# Drive_X.net
KiCad netlist of a schematic drawn in Altium Designer
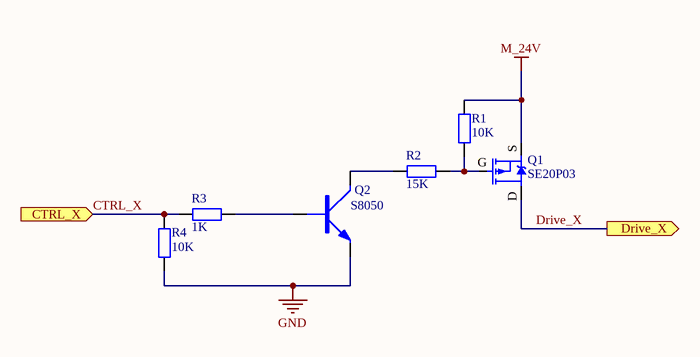
[diagram p0: Drive_X.SchDoc]

(export (version "E")
  (design (tool "Eeschema 10.0.6"))
  (components
    (comp (ref "Q1")
      (value "SE20P03")
      (footprint "TO252")
      (description "P沟道场效应管")
      (libsource (lib "MOS管") (part "P-MOS"))
    )
    (comp (ref "Q2")
      (value "S8050")
      (footprint "SOT-23")
      (description "NPN三极管")
      (libsource (lib "三极管") (part "NPN"))
    )
    (comp (ref "R1")
      (value "10K")
      (footprint "R 0603")
      (description "贴片电阻")
      (fields (field (name "版权归属") "源创客"))
      (libsource (lib "源创客") (part "R"))
    )
    (comp (ref "R2")
      (value "15K")
      (footprint "R 0603")
      (description "贴片电阻")
      (fields (field (name "版权归属") "源创客"))
      (libsource (lib "源创客") (part "R"))
    )
    (comp (ref "R3")
      (value "1K")
      (footprint "R 0603")
      (description "贴片电阻")
      (fields (field (name "版权归属") "源创客"))
      (libsource (lib "源创客") (part "R"))
    )
    (comp (ref "R4")
      (value "10K")
      (footprint "R 0603")
      (description "贴片电阻")
      (fields (field (name "版权归属") "源创客"))
      (libsource (lib "源创客") (part "R"))
    )
  )
  (nets
    (net (code "1") (name "/CTRL_X") (class "Default")
      (node (ref "R3") (pin "1") (pinfunction "1_1") (pintype "passive"))
      (node (ref "R4") (pin "1") (pinfunction "1_1") (pintype "passive"))
    )
    (net (code "2") (name "/Drive_X") (class "Default")
      (node (ref "Q1") (pin "D") (pinfunction "D_D") (pintype "passive"))
    )
    (net (code "3") (name "GND") (class "Default")
      (node (ref "Q2") (pin "E") (pinfunction "E_E") (pintype "passive"))
      (node (ref "R4") (pin "2") (pinfunction "2_2") (pintype "passive"))
    )
    (net (code "4") (name "M_24V") (class "Default")
      (node (ref "Q1") (pin "S") (pinfunction "S_S") (pintype "passive"))
      (node (ref "R1") (pin "2") (pinfunction "2_2") (pintype "passive"))
    )
    (net (code "5") (name "Net-(Q1-PadG)") (class "Default")
      (node (ref "Q1") (pin "G") (pinfunction "G_G") (pintype "passive"))
      (node (ref "R1") (pin "1") (pinfunction "1_1") (pintype "passive"))
      (node (ref "R2") (pin "1") (pinfunction "1_1") (pintype "passive"))
    )
    (net (code "6") (name "Net-(Q2-PadB)") (class "Default")
      (node (ref "Q2") (pin "B") (pinfunction "B_B") (pintype "passive"))
      (node (ref "R3") (pin "2") (pinfunction "2_2") (pintype "passive"))
    )
    (net (code "7") (name "Net-(Q2-PadC)") (class "Default")
      (node (ref "Q2") (pin "C") (pinfunction "C_C") (pintype "passive"))
      (node (ref "R2") (pin "2") (pinfunction "2_2") (pintype "passive"))
    )
  )
)
